# ProPrj___2025-03-06.net
KiCad netlist of a schematic drawn in EasyEDA Pro
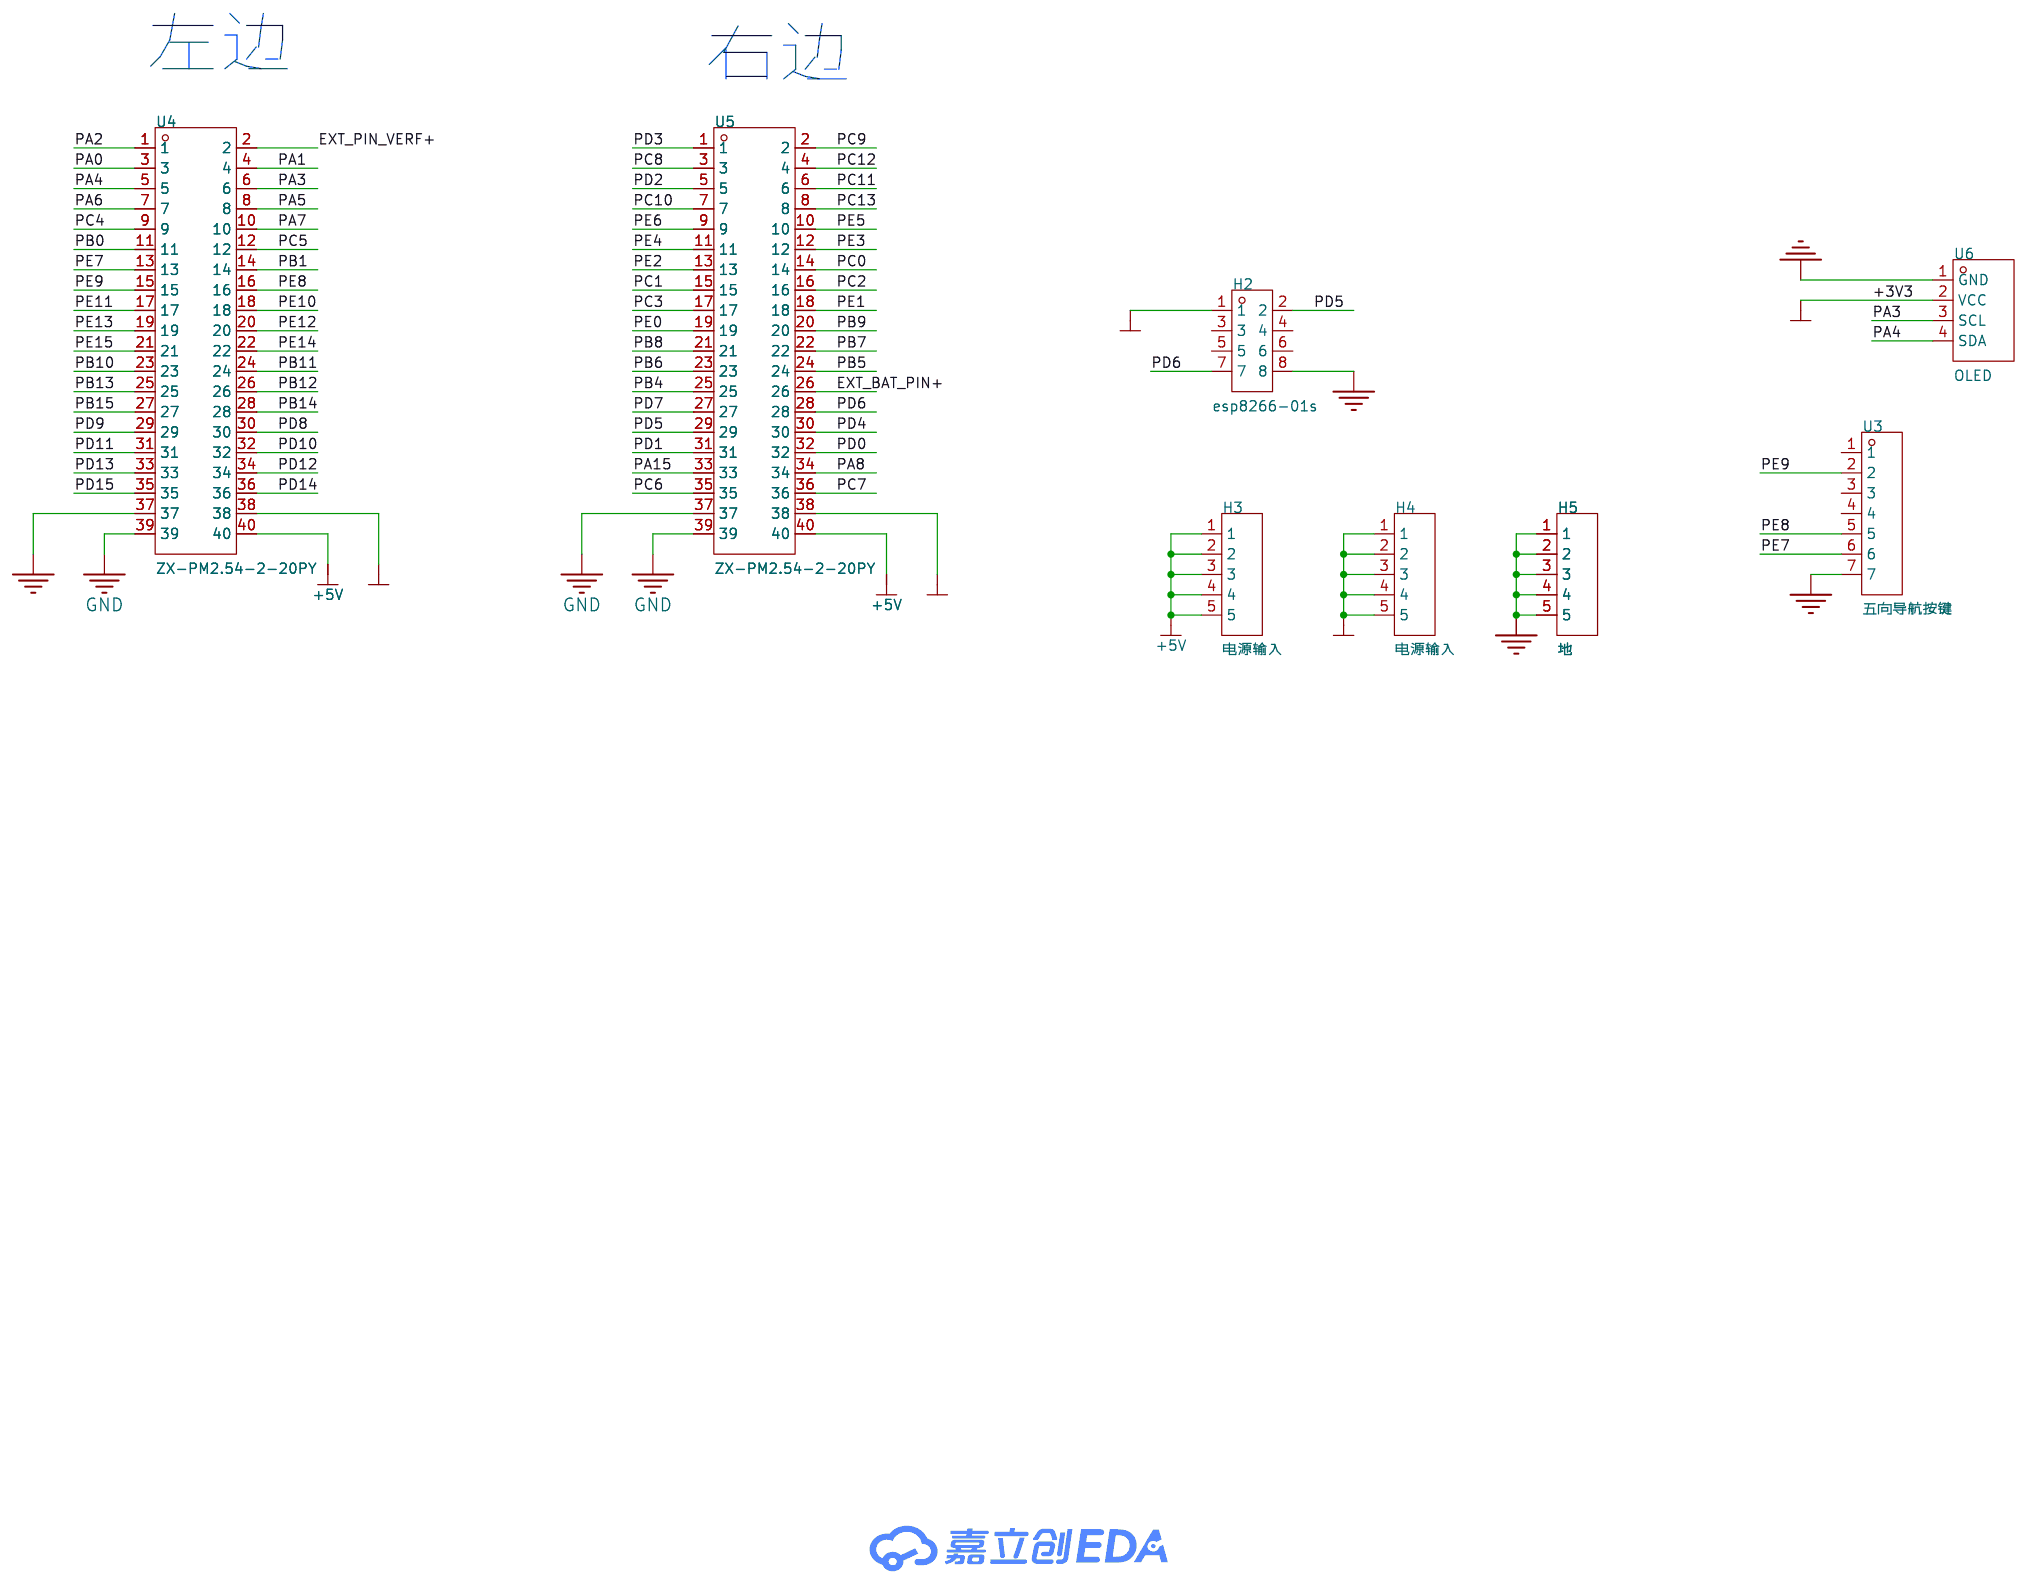
[diagram p0: schematic sheet]

(export (version "E")
  (design (tool "Eeschema 10.0.6"))
  (components
    (comp (ref "H2")
      (value "esp8266-01s")
      (footprint "easyedapro:HDR-TH_8P-P2.54-V-F-R2-C4-S2.54")
      (fields (field (name "Manufacturer Part") "PM254V-12-08-H85") (field (name "Manufacturer") "XFCN(兴飞)"))
      (libsource (lib "easyedapro") (part "PM254V-12-08-H85_C2834799"))
    )
    (comp (ref "H3")
      (value "电源输入")
      (footprint "easyedapro:HDR-TH_5P-P2.54-V-M")
      (fields (field (name "Manufacturer Part") "PZ254V-11-05P") (field (name "Manufacturer") "XFCN(兴飞)"))
      (libsource (lib "easyedapro") (part "PZ254V-11-05P"))
    )
    (comp (ref "H4")
      (value "电源输入")
      (footprint "easyedapro:HDR-TH_5P-P2.54-V-M")
      (fields (field (name "Manufacturer Part") "PZ254V-11-05P") (field (name "Manufacturer") "XFCN(兴飞)"))
      (libsource (lib "easyedapro") (part "PZ254V-11-05P"))
    )
    (comp (ref "H5")
      (value "地")
      (footprint "easyedapro:HDR-TH_5P-P2.54-V-M")
      (fields (field (name "Manufacturer Part") "PZ254V-11-05P") (field (name "Manufacturer") "XFCN(兴飞)"))
      (libsource (lib "easyedapro") (part "PZ254V-11-05P"))
    )
    (comp (ref "U3")
      (value "五向导航按键")
      (footprint "easyedapro:HDR-TH_7P-P2.54-H-F-W10.0-N")
      (fields
        (field (name "Manufacturer Part") "PM254-1-07-W-8.5")
        (field (name "Manufacturer") "HCTL(华灿天禄)")
      )
      (libsource (lib "easyedapro") (part "PM254-1-07-W-8.5"))
    )
    (comp (ref "U4")
      (value "ZX-PM2.54-2-20PY")
      (footprint "easyedapro:HDR-TH_40P-P2.54-V-F-R2-C20-S2.54")
      (fields (field (name "Manufacturer") "Megastar(兆星)"))
      (libsource (lib "easyedapro") (part "ZX-PM2.54-2-20PY"))
    )
    (comp (ref "U5")
      (value "ZX-PM2.54-2-20PY")
      (footprint "easyedapro:HDR-TH_40P-P2.54-V-F-R2-C20-S2.54")
      (fields (field (name "Manufacturer") "Megastar(兆星)"))
      (libsource (lib "easyedapro") (part "ZX-PM2.54-2-20PY"))
    )
    (comp (ref "U6")
      (value "OLED")
      (footprint "easyedapro:OLED-TH_L27.8-W27.2-P2.54_C9900033791")
      (description "主控芯片:SSD1315;接口类型:I2C;尺寸(inch):0.96;像素分辨率:128x64;")
      (fields (field (name "Manufacturer Part") "HS96L03W2C03") (field (name "Manufacturer") "HS(汉昇)"))
      (libsource (lib "easyedapro") (part "HS96L03W2C03"))
    )
  )
  (nets
    (net (code "1") (name "+3V3") (class "Default")
      (node (ref "H2") (pin "1") (pinfunction "1_1") (pintype "unspecified"))
      (node (ref "H4") (pin "1") (pinfunction "1_1") (pintype "unspecified"))
      (node (ref "H4") (pin "2") (pinfunction "2_2") (pintype "unspecified"))
      (node (ref "H4") (pin "3") (pinfunction "3_3") (pintype "unspecified"))
      (node (ref "H4") (pin "4") (pinfunction "4_4") (pintype "unspecified"))
      (node (ref "H4") (pin "5") (pinfunction "5_5") (pintype "unspecified"))
      (node (ref "U4") (pin "38") (pinfunction "38_38") (pintype "unspecified"))
      (node (ref "U5") (pin "38") (pinfunction "38_38") (pintype "unspecified"))
      (node (ref "U6") (pin "2") (pinfunction "VCC_2") (pintype "unspecified"))
    )
    (net (code "2") (name "+5V") (class "Default")
      (node (ref "H3") (pin "1") (pinfunction "1_1") (pintype "unspecified"))
      (node (ref "H3") (pin "2") (pinfunction "2_2") (pintype "unspecified"))
      (node (ref "H3") (pin "3") (pinfunction "3_3") (pintype "unspecified"))
      (node (ref "H3") (pin "4") (pinfunction "4_4") (pintype "unspecified"))
      (node (ref "H3") (pin "5") (pinfunction "5_5") (pintype "unspecified"))
      (node (ref "U4") (pin "40") (pinfunction "40_40") (pintype "unspecified"))
      (node (ref "U5") (pin "40") (pinfunction "40_40") (pintype "unspecified"))
    )
    (net (code "3") (name "/EXT_BAT_PIN+") (class "Default")
      (node (ref "U5") (pin "26") (pinfunction "26_26") (pintype "unspecified"))
    )
    (net (code "4") (name "/EXT_PIN_VERF+") (class "Default")
      (node (ref "U4") (pin "2") (pinfunction "2_2") (pintype "unspecified"))
    )
    (net (code "5") (name "/PA0") (class "Default")
      (node (ref "U4") (pin "3") (pinfunction "3_3") (pintype "unspecified"))
    )
    (net (code "6") (name "/PA1") (class "Default")
      (node (ref "U4") (pin "4") (pinfunction "4_4") (pintype "unspecified"))
    )
    (net (code "7") (name "/PA2") (class "Default")
      (node (ref "U4") (pin "1") (pinfunction "1_1") (pintype "unspecified"))
    )
    (net (code "8") (name "/PA3") (class "Default")
      (node (ref "U4") (pin "6") (pinfunction "6_6") (pintype "unspecified"))
      (node (ref "U6") (pin "3") (pinfunction "SCL_3") (pintype "unspecified"))
    )
    (net (code "9") (name "/PA4") (class "Default")
      (node (ref "U4") (pin "5") (pinfunction "5_5") (pintype "unspecified"))
      (node (ref "U6") (pin "4") (pinfunction "SDA_4") (pintype "unspecified"))
    )
    (net (code "10") (name "/PA5") (class "Default")
      (node (ref "U4") (pin "8") (pinfunction "8_8") (pintype "unspecified"))
    )
    (net (code "11") (name "/PA6") (class "Default")
      (node (ref "U4") (pin "7") (pinfunction "7_7") (pintype "unspecified"))
    )
    (net (code "12") (name "/PA7") (class "Default")
      (node (ref "U4") (pin "10") (pinfunction "10_10") (pintype "unspecified"))
    )
    (net (code "13") (name "/PA8") (class "Default")
      (node (ref "U5") (pin "34") (pinfunction "34_34") (pintype "unspecified"))
    )
    (net (code "14") (name "/PA15") (class "Default")
      (node (ref "U5") (pin "33") (pinfunction "33_33") (pintype "unspecified"))
    )
    (net (code "15") (name "/PB0") (class "Default")
      (node (ref "U4") (pin "11") (pinfunction "11_11") (pintype "unspecified"))
    )
    (net (code "16") (name "/PB1") (class "Default")
      (node (ref "U4") (pin "14") (pinfunction "14_14") (pintype "unspecified"))
    )
    (net (code "17") (name "/PB4") (class "Default")
      (node (ref "U5") (pin "25") (pinfunction "25_25") (pintype "unspecified"))
    )
    (net (code "18") (name "/PB5") (class "Default")
      (node (ref "U5") (pin "24") (pinfunction "24_24") (pintype "unspecified"))
    )
    (net (code "19") (name "/PB6") (class "Default")
      (node (ref "U5") (pin "23") (pinfunction "23_23") (pintype "unspecified"))
    )
    (net (code "20") (name "/PB7") (class "Default")
      (node (ref "U5") (pin "22") (pinfunction "22_22") (pintype "unspecified"))
    )
    (net (code "21") (name "/PB8") (class "Default")
      (node (ref "U5") (pin "21") (pinfunction "21_21") (pintype "unspecified"))
    )
    (net (code "22") (name "/PB9") (class "Default")
      (node (ref "U5") (pin "20") (pinfunction "20_20") (pintype "unspecified"))
    )
    (net (code "23") (name "/PB10") (class "Default")
      (node (ref "U4") (pin "23") (pinfunction "23_23") (pintype "unspecified"))
    )
    (net (code "24") (name "/PB11") (class "Default")
      (node (ref "U4") (pin "24") (pinfunction "24_24") (pintype "unspecified"))
    )
    (net (code "25") (name "/PB12") (class "Default")
      (node (ref "U4") (pin "26") (pinfunction "26_26") (pintype "unspecified"))
    )
    (net (code "26") (name "/PB13") (class "Default")
      (node (ref "U4") (pin "25") (pinfunction "25_25") (pintype "unspecified"))
    )
    (net (code "27") (name "/PB14") (class "Default")
      (node (ref "U4") (pin "28") (pinfunction "28_28") (pintype "unspecified"))
    )
    (net (code "28") (name "/PB15") (class "Default")
      (node (ref "U4") (pin "27") (pinfunction "27_27") (pintype "unspecified"))
    )
    (net (code "29") (name "/PC0") (class "Default")
      (node (ref "U5") (pin "14") (pinfunction "14_14") (pintype "unspecified"))
    )
    (net (code "30") (name "/PC1") (class "Default")
      (node (ref "U5") (pin "15") (pinfunction "15_15") (pintype "unspecified"))
    )
    (net (code "31") (name "/PC2") (class "Default")
      (node (ref "U5") (pin "16") (pinfunction "16_16") (pintype "unspecified"))
    )
    (net (code "32") (name "/PC3") (class "Default")
      (node (ref "U5") (pin "17") (pinfunction "17_17") (pintype "unspecified"))
    )
    (net (code "33") (name "/PC4") (class "Default")
      (node (ref "U4") (pin "9") (pinfunction "9_9") (pintype "unspecified"))
    )
    (net (code "34") (name "/PC5") (class "Default")
      (node (ref "U4") (pin "12") (pinfunction "12_12") (pintype "unspecified"))
    )
    (net (code "35") (name "/PC6") (class "Default")
      (node (ref "U5") (pin "35") (pinfunction "35_35") (pintype "unspecified"))
    )
    (net (code "36") (name "/PC7") (class "Default")
      (node (ref "U5") (pin "36") (pinfunction "36_36") (pintype "unspecified"))
    )
    (net (code "37") (name "/PC8") (class "Default")
      (node (ref "U5") (pin "3") (pinfunction "3_3") (pintype "unspecified"))
    )
    (net (code "38") (name "/PC9") (class "Default")
      (node (ref "U5") (pin "2") (pinfunction "2_2") (pintype "unspecified"))
    )
    (net (code "39") (name "/PC10") (class "Default")
      (node (ref "U5") (pin "7") (pinfunction "7_7") (pintype "unspecified"))
    )
    (net (code "40") (name "/PC11") (class "Default")
      (node (ref "U5") (pin "6") (pinfunction "6_6") (pintype "unspecified"))
    )
    (net (code "41") (name "/PC12") (class "Default")
      (node (ref "U5") (pin "4") (pinfunction "4_4") (pintype "unspecified"))
    )
    (net (code "42") (name "/PC13") (class "Default")
      (node (ref "U5") (pin "8") (pinfunction "8_8") (pintype "unspecified"))
    )
    (net (code "43") (name "/PD0") (class "Default")
      (node (ref "U5") (pin "32") (pinfunction "32_32") (pintype "unspecified"))
    )
    (net (code "44") (name "/PD1") (class "Default")
      (node (ref "U5") (pin "31") (pinfunction "31_31") (pintype "unspecified"))
    )
    (net (code "45") (name "/PD2") (class "Default")
      (node (ref "U5") (pin "5") (pinfunction "5_5") (pintype "unspecified"))
    )
    (net (code "46") (name "/PD3") (class "Default")
      (node (ref "U5") (pin "1") (pinfunction "1_1") (pintype "unspecified"))
    )
    (net (code "47") (name "/PD4") (class "Default")
      (node (ref "U5") (pin "30") (pinfunction "30_30") (pintype "unspecified"))
    )
    (net (code "48") (name "/PD5") (class "Default")
      (node (ref "H2") (pin "2") (pinfunction "2_2") (pintype "unspecified"))
      (node (ref "U5") (pin "29") (pinfunction "29_29") (pintype "unspecified"))
    )
    (net (code "49") (name "/PD6") (class "Default")
      (node (ref "H2") (pin "7") (pinfunction "7_7") (pintype "unspecified"))
      (node (ref "U5") (pin "28") (pinfunction "28_28") (pintype "unspecified"))
    )
    (net (code "50") (name "/PD7") (class "Default")
      (node (ref "U5") (pin "27") (pinfunction "27_27") (pintype "unspecified"))
    )
    (net (code "51") (name "/PD8") (class "Default")
      (node (ref "U4") (pin "30") (pinfunction "30_30") (pintype "unspecified"))
    )
    (net (code "52") (name "/PD9") (class "Default")
      (node (ref "U4") (pin "29") (pinfunction "29_29") (pintype "unspecified"))
    )
    (net (code "53") (name "/PD10") (class "Default")
      (node (ref "U4") (pin "32") (pinfunction "32_32") (pintype "unspecified"))
    )
    (net (code "54") (name "/PD11") (class "Default")
      (node (ref "U4") (pin "31") (pinfunction "31_31") (pintype "unspecified"))
    )
    (net (code "55") (name "/PD12") (class "Default")
      (node (ref "U4") (pin "34") (pinfunction "34_34") (pintype "unspecified"))
    )
    (net (code "56") (name "/PD13") (class "Default")
      (node (ref "U4") (pin "33") (pinfunction "33_33") (pintype "unspecified"))
    )
    (net (code "57") (name "/PD14") (class "Default")
      (node (ref "U4") (pin "36") (pinfunction "36_36") (pintype "unspecified"))
    )
    (net (code "58") (name "/PD15") (class "Default")
      (node (ref "U4") (pin "35") (pinfunction "35_35") (pintype "unspecified"))
    )
    (net (code "59") (name "/PE0") (class "Default")
      (node (ref "U5") (pin "19") (pinfunction "19_19") (pintype "unspecified"))
    )
    (net (code "60") (name "/PE1") (class "Default")
      (node (ref "U5") (pin "18") (pinfunction "18_18") (pintype "unspecified"))
    )
    (net (code "61") (name "/PE2") (class "Default")
      (node (ref "U5") (pin "13") (pinfunction "13_13") (pintype "unspecified"))
    )
    (net (code "62") (name "/PE3") (class "Default")
      (node (ref "U5") (pin "12") (pinfunction "12_12") (pintype "unspecified"))
    )
    (net (code "63") (name "/PE4") (class "Default")
      (node (ref "U5") (pin "11") (pinfunction "11_11") (pintype "unspecified"))
    )
    (net (code "64") (name "/PE5") (class "Default")
      (node (ref "U5") (pin "10") (pinfunction "10_10") (pintype "unspecified"))
    )
    (net (code "65") (name "/PE6") (class "Default")
      (node (ref "U5") (pin "9") (pinfunction "9_9") (pintype "unspecified"))
    )
    (net (code "66") (name "/PE7") (class "Default")
      (node (ref "U3") (pin "6") (pinfunction "6_6") (pintype "unspecified"))
      (node (ref "U4") (pin "13") (pinfunction "13_13") (pintype "unspecified"))
    )
    (net (code "67") (name "/PE8") (class "Default")
      (node (ref "U3") (pin "5") (pinfunction "5_5") (pintype "unspecified"))
      (node (ref "U4") (pin "16") (pinfunction "16_16") (pintype "unspecified"))
    )
    (net (code "68") (name "/PE9") (class "Default")
      (node (ref "U3") (pin "2") (pinfunction "2_2") (pintype "unspecified"))
      (node (ref "U4") (pin "15") (pinfunction "15_15") (pintype "unspecified"))
    )
    (net (code "69") (name "/PE10") (class "Default")
      (node (ref "U4") (pin "18") (pinfunction "18_18") (pintype "unspecified"))
    )
    (net (code "70") (name "/PE11") (class "Default")
      (node (ref "U4") (pin "17") (pinfunction "17_17") (pintype "unspecified"))
    )
    (net (code "71") (name "/PE12") (class "Default")
      (node (ref "U4") (pin "20") (pinfunction "20_20") (pintype "unspecified"))
    )
    (net (code "72") (name "/PE13") (class "Default")
      (node (ref "U4") (pin "19") (pinfunction "19_19") (pintype "unspecified"))
    )
    (net (code "73") (name "/PE14") (class "Default")
      (node (ref "U4") (pin "22") (pinfunction "22_22") (pintype "unspecified"))
    )
    (net (code "74") (name "/PE15") (class "Default")
      (node (ref "U4") (pin "21") (pinfunction "21_21") (pintype "unspecified"))
    )
    (net (code "75") (name "AGND") (class "Default")
      (node (ref "U4") (pin "37") (pinfunction "37_37") (pintype "unspecified"))
    )
    (net (code "76") (name "GND") (class "Default")
      (node (ref "H2") (pin "8") (pinfunction "8_8") (pintype "unspecified"))
      (node (ref "H5") (pin "1") (pinfunction "1_1") (pintype "unspecified"))
      (node (ref "H5") (pin "2") (pinfunction "2_2") (pintype "unspecified"))
      (node (ref "H5") (pin "3") (pinfunction "3_3") (pintype "unspecified"))
      (node (ref "H5") (pin "4") (pinfunction "4_4") (pintype "unspecified"))
      (node (ref "H5") (pin "5") (pinfunction "5_5") (pintype "unspecified"))
      (node (ref "U3") (pin "7") (pinfunction "7_7") (pintype "unspecified"))
      (node (ref "U4") (pin "39") (pinfunction "39_39") (pintype "unspecified"))
      (node (ref "U5") (pin "37") (pinfunction "37_37") (pintype "unspecified"))
      (node (ref "U5") (pin "39") (pinfunction "39_39") (pintype "unspecified"))
      (node (ref "U6") (pin "1") (pinfunction "GND_1") (pintype "unspecified"))
    )
    (net (code "77") (name "unconnected-(H2-Pad3)") (class "Default")
      (node (ref "H2") (pin "3") (pinfunction "3_3") (pintype "unspecified"))
    )
    (net (code "78") (name "unconnected-(H2-Pad4)") (class "Default")
      (node (ref "H2") (pin "4") (pinfunction "4_4") (pintype "unspecified"))
    )
    (net (code "79") (name "unconnected-(H2-Pad5)") (class "Default")
      (node (ref "H2") (pin "5") (pinfunction "5_5") (pintype "unspecified"))
    )
    (net (code "80") (name "unconnected-(H2-Pad6)") (class "Default")
      (node (ref "H2") (pin "6") (pinfunction "6_6") (pintype "unspecified"))
    )
    (net (code "81") (name "unconnected-(U3-Pad1)") (class "Default")
      (node (ref "U3") (pin "1") (pinfunction "1_1") (pintype "unspecified"))
    )
    (net (code "82") (name "unconnected-(U3-Pad3)") (class "Default")
      (node (ref "U3") (pin "3") (pinfunction "3_3") (pintype "unspecified"))
    )
    (net (code "83") (name "unconnected-(U3-Pad4)") (class "Default")
      (node (ref "U3") (pin "4") (pinfunction "4_4") (pintype "unspecified"))
    )
  )
)
